# Power.net
KiCad netlist of a schematic drawn in Altium Designer
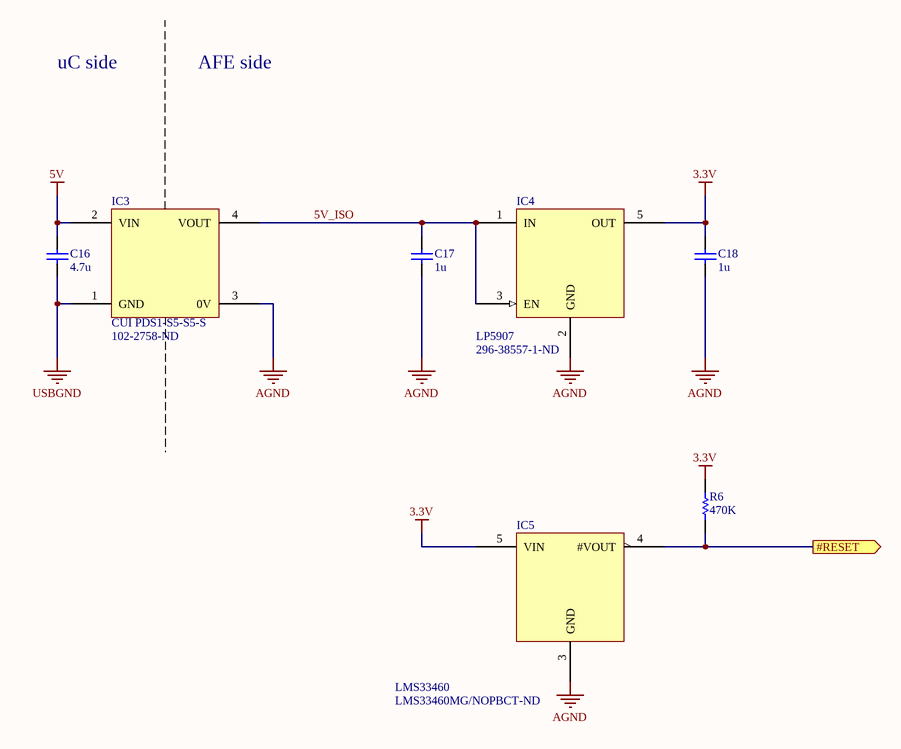
[diagram p0: Power.SchDoc]

(export (version "E")
  (design (tool "Eeschema 10.0.6"))
  (components
    (comp (ref "C16") (value "4.7u") (footprint "0805 CAP") (libsource (lib "B105lib") (part "Cap")))
    (comp (ref "C17") (value "1u") (footprint "0805 CAP") (libsource (lib "B105lib") (part "Cap")))
    (comp (ref "C18") (value "1u") (footprint "0805 CAP") (libsource (lib "B105lib") (part "Cap")))
    (comp (ref "IC3")
      (value "CUI PDS1-S5-S5-S")
      (footprint "SIL4")
      (fields (field (name "SUPPLIER PART NUMBER 1") "102-2758-ND"))
      (libsource (lib "ECG_EMG") (part "CUI PDS1-S5-S5-S"))
    )
    (comp (ref "IC4")
      (value "LP5907")
      (footprint "SOT95P280X145-5N")
      (fields (field (name "SUPPLIER PART NUMBER 1") "296-38557-1-ND"))
      (libsource (lib "ECG_EMG") (part "LP5907"))
    )
    (comp (ref "IC5")
      (value "LMS33460")
      (footprint "SOT65P210X110-5N")
      (fields (field (name "SUPPLIER PART NUMBER 1") "LMS33460MG/NOPBCT-ND"))
      (libsource (lib "ECG_EMG") (part "LMS33460"))
    )
    (comp (ref "R6") (value "470K") (footprint "0805 Res") (libsource (lib "B105lib") (part "Res")))
  )
  (nets
    (net (code "1") (name "/#RESET") (class "Default")
      (node (ref "IC5") (pin "4") (pinfunction "#VOUT_4") (pintype "open_collector"))
      (node (ref "R6") (pin "1") (pinfunction "1_1") (pintype "passive"))
    )
    (net (code "2") (name "/5V_ISO") (class "Default")
      (node (ref "C17") (pin "2") (pinfunction "2_2") (pintype "passive"))
      (node (ref "IC3") (pin "4") (pinfunction "VOUT_4") (pintype "power_in"))
      (node (ref "IC4") (pin "1") (pinfunction "IN_1") (pintype "power_in"))
      (node (ref "IC4") (pin "3") (pinfunction "EN_3") (pintype "input"))
    )
    (net (code "3") (name "3.3V") (class "Default")
      (node (ref "C18") (pin "2") (pinfunction "2_2") (pintype "passive"))
      (node (ref "IC4") (pin "5") (pinfunction "OUT_5") (pintype "power_in"))
      (node (ref "IC5") (pin "5") (pinfunction "VIN_5") (pintype "power_in"))
      (node (ref "R6") (pin "2") (pinfunction "2_2") (pintype "passive"))
    )
    (net (code "4") (name "5V") (class "Default")
      (node (ref "C16") (pin "2") (pinfunction "2_2") (pintype "passive"))
      (node (ref "IC3") (pin "2") (pinfunction "VIN_2") (pintype "power_in"))
    )
    (net (code "5") (name "AGND") (class "Default")
      (node (ref "C17") (pin "1") (pinfunction "1_1") (pintype "passive"))
      (node (ref "C18") (pin "1") (pinfunction "1_1") (pintype "passive"))
      (node (ref "IC3") (pin "3") (pinfunction "0V_3") (pintype "power_in"))
      (node (ref "IC4") (pin "2") (pinfunction "GND_2") (pintype "power_in"))
      (node (ref "IC5") (pin "3") (pinfunction "GND_3") (pintype "power_in"))
    )
    (net (code "6") (name "USBGND") (class "Default")
      (node (ref "C16") (pin "1") (pinfunction "1_1") (pintype "passive"))
      (node (ref "IC3") (pin "1") (pinfunction "GND_1") (pintype "power_in"))
    )
  )
)
